# 2out_16A_bi_TS-ARM_V1_0.net
KiCad netlist of a schematic drawn in EAGLE
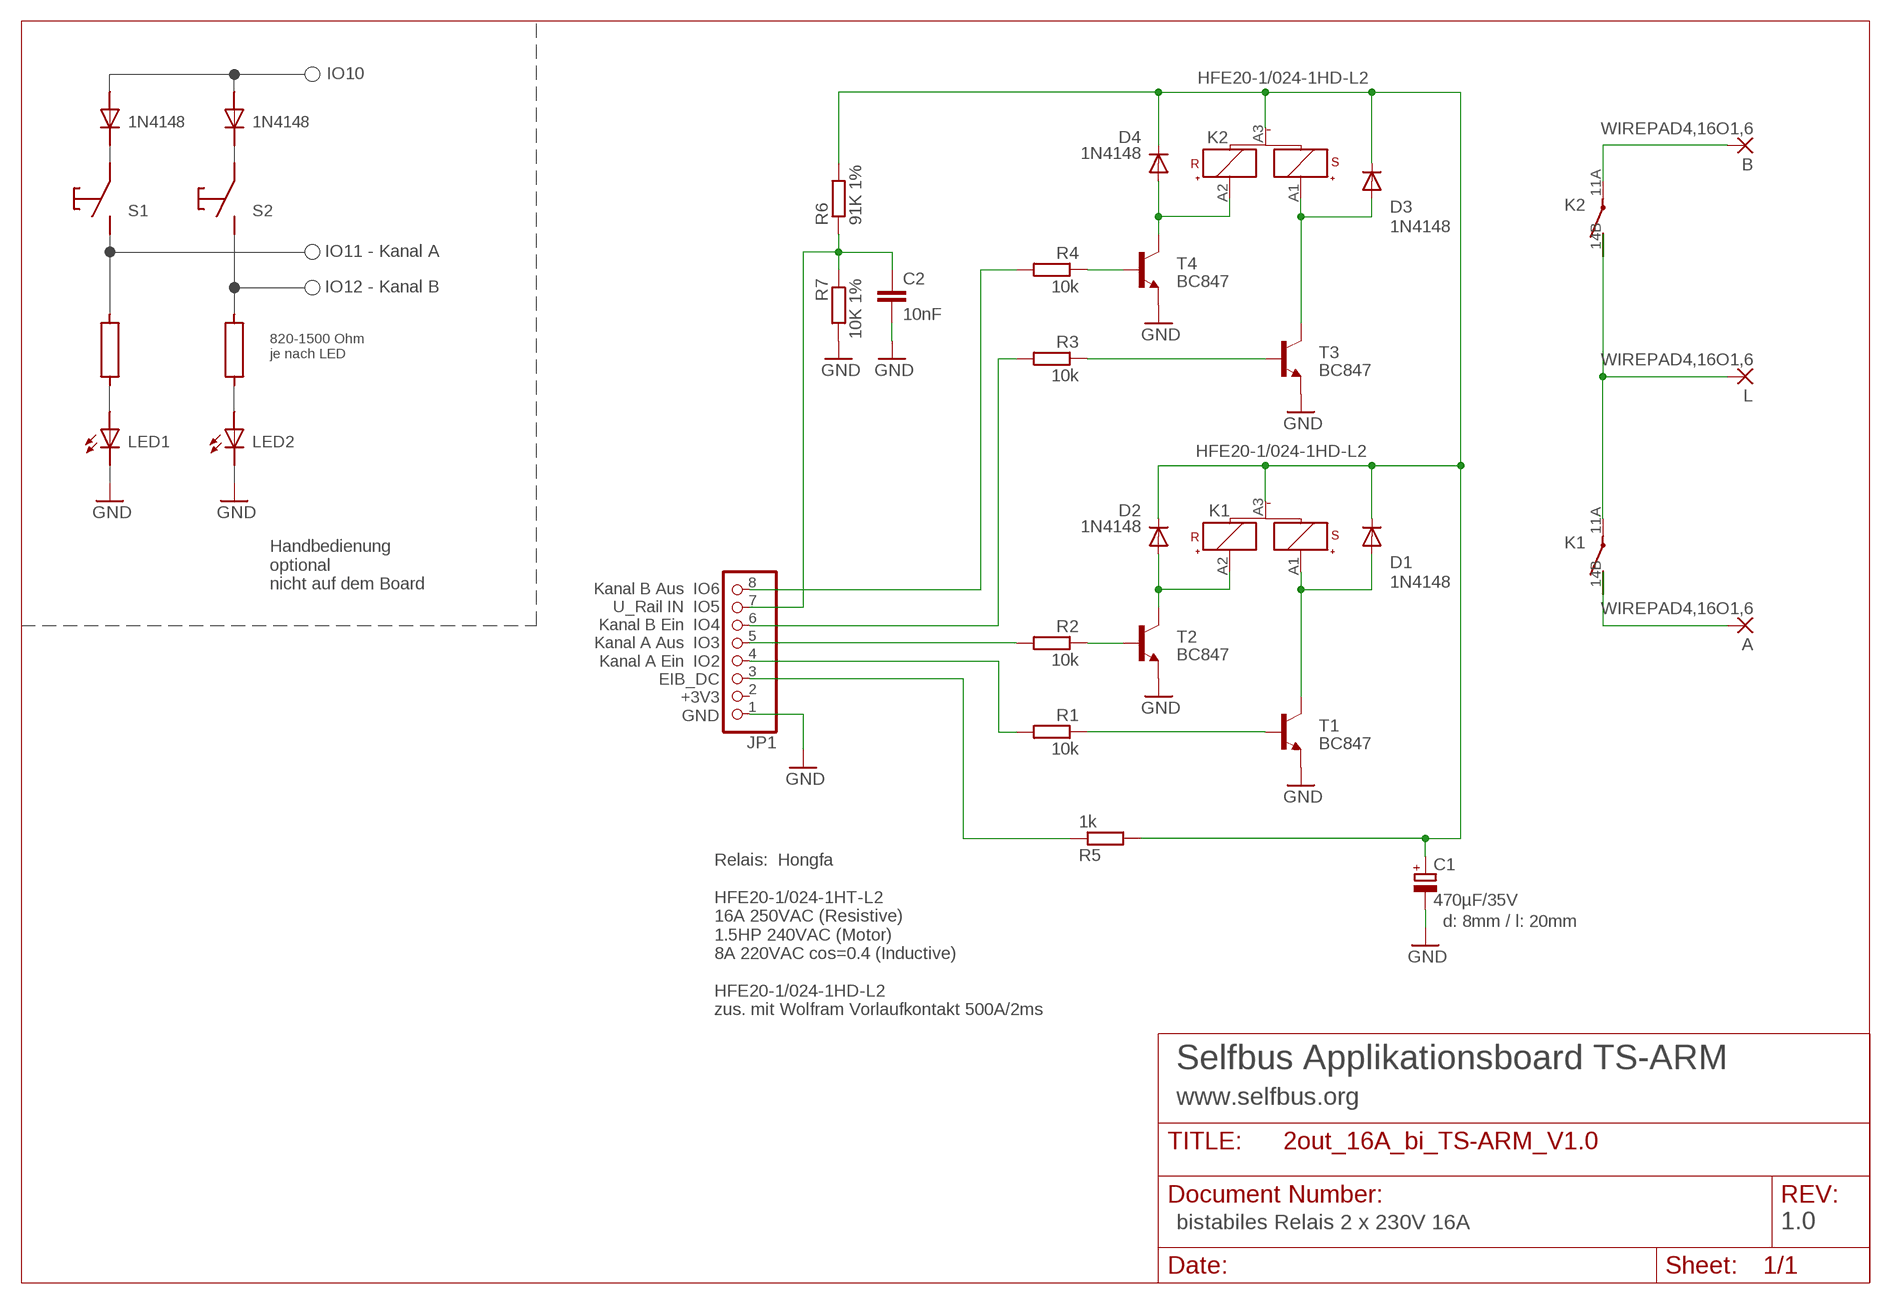
[diagram p0: schematic, sheet 1]

(export (version "E")
  (design (tool "Eeschema 10.0.6"))
  (components
    (comp (ref "A")
      (value "WIREPAD4,16O1,6")
      (footprint "eagle-import:4,16O1,6")
      (libsource (lib "eagle-import") (part "WIREPAD4,16O1,6"))
    )
    (comp (ref "B")
      (value "WIREPAD4,16O1,6")
      (footprint "eagle-import:4,16O1,6")
      (libsource (lib "eagle-import") (part "WIREPAD4,16O1,6"))
    )
    (comp (ref "C1")
      (value "470µF/35V")
      (footprint "eagle-import:E3,5-8")
      (libsource (lib "eagle-import") (part "CPOL-EUE3.5-8"))
    )
    (comp (ref "C2")
      (value "10nF")
      (footprint "eagle-import:C1206K")
      (libsource (lib "eagle-import") (part "C-EUC1206K"))
    )
    (comp (ref "D1")
      (value "1N4148")
      (footprint "eagle-import:MINIMELF")
      (libsource (lib "eagle-import") (part "DIODE-MINIMELF"))
    )
    (comp (ref "D2")
      (value "1N4148")
      (footprint "eagle-import:MINIMELF")
      (libsource (lib "eagle-import") (part "DIODE-MINIMELF"))
    )
    (comp (ref "D3")
      (value "1N4148")
      (footprint "eagle-import:MINIMELF")
      (libsource (lib "eagle-import") (part "DIODE-MINIMELF"))
    )
    (comp (ref "D4")
      (value "1N4148")
      (footprint "eagle-import:MINIMELF")
      (libsource (lib "eagle-import") (part "DIODE-MINIMELF"))
    )
    (comp (ref "JP1")
      (value "PINHD-1X8")
      (footprint "eagle-import:1X08")
      (libsource (lib "eagle-import") (part "PINHD-1X8"))
    )
    (comp (ref "K1")
      (value "HFE20-1/024-1HD-L2")
      (footprint "eagle-import:RT1-BI")
      (fields (field (name "MPN") "RT314F24"))
      (libsource (lib "eagle-import") (part "RT?F31424"))
    )
    (comp (ref "K2")
      (value "HFE20-1/024-1HD-L2")
      (footprint "eagle-import:RT1-BI")
      (fields (field (name "MPN") "RT314F24"))
      (libsource (lib "eagle-import") (part "RT?F31424"))
    )
    (comp (ref "L")
      (value "WIREPAD4,16O1,6")
      (footprint "eagle-import:4,16O1,6")
      (libsource (lib "eagle-import") (part "WIREPAD4,16O1,6"))
    )
    (comp (ref "R1")
      (value "10k")
      (footprint "eagle-import:M1206")
      (libsource (lib "eagle-import") (part "R-EU_M1206"))
    )
    (comp (ref "R2")
      (value "10k")
      (footprint "eagle-import:M1206")
      (libsource (lib "eagle-import") (part "R-EU_M1206"))
    )
    (comp (ref "R3")
      (value "10k")
      (footprint "eagle-import:M1206")
      (libsource (lib "eagle-import") (part "R-EU_M1206"))
    )
    (comp (ref "R4")
      (value "10k")
      (footprint "eagle-import:M1206")
      (libsource (lib "eagle-import") (part "R-EU_M1206"))
    )
    (comp (ref "R5")
      (value "1k")
      (footprint "eagle-import:M1206")
      (libsource (lib "eagle-import") (part "R-EU_M1206"))
    )
    (comp (ref "R6")
      (value "91K 1%")
      (footprint "eagle-import:M1206")
      (libsource (lib "eagle-import") (part "R-EU_M1206"))
    )
    (comp (ref "R7")
      (value "10K 1%")
      (footprint "eagle-import:M1206")
      (libsource (lib "eagle-import") (part "R-EU_M1206"))
    )
    (comp (ref "T1")
      (value "BC847")
      (footprint "eagle-import:SOT23")
      (libsource (lib "eagle-import") (part "BC847"))
    )
    (comp (ref "T2")
      (value "BC847")
      (footprint "eagle-import:SOT23")
      (libsource (lib "eagle-import") (part "BC847"))
    )
    (comp (ref "T3")
      (value "BC847")
      (footprint "eagle-import:SOT23")
      (libsource (lib "eagle-import") (part "BC847"))
    )
    (comp (ref "T4")
      (value "BC847")
      (footprint "eagle-import:SOT23")
      (libsource (lib "eagle-import") (part "BC847"))
    )
    (comp (ref "U$1")
      (value "R_NUR_SCHALTPLAN")
      (footprint "eagle-import:LEER")
      (libsource (lib "eagle-import") (part "R_NUR_SCHALTPLAN"))
    )
    (comp (ref "U$2")
      (value "TASTE_NUR_SCHALTPLAN")
      (footprint "eagle-import:LEER")
      (libsource (lib "eagle-import") (part "TASTE_NUR_SCHALTPLAN"))
    )
    (comp (ref "U$3")
      (value "LED_NUR_SCHALTPLAN")
      (footprint "eagle-import:LEER")
      (libsource (lib "eagle-import") (part "LED_NUR_SCHALTPLAN"))
    )
    (comp (ref "U$4")
      (value "DIODE_NUR_SCHALTPLAN")
      (footprint "eagle-import:LEER")
      (libsource (lib "eagle-import") (part "DIODE_NUR_SCHALTPLAN"))
    )
    (comp (ref "U$5")
      (value "R_NUR_SCHALTPLAN")
      (footprint "eagle-import:LEER")
      (libsource (lib "eagle-import") (part "R_NUR_SCHALTPLAN"))
    )
    (comp (ref "U$6")
      (value "TASTE_NUR_SCHALTPLAN")
      (footprint "eagle-import:LEER")
      (libsource (lib "eagle-import") (part "TASTE_NUR_SCHALTPLAN"))
    )
    (comp (ref "U$7")
      (value "LED_NUR_SCHALTPLAN")
      (footprint "eagle-import:LEER")
      (libsource (lib "eagle-import") (part "LED_NUR_SCHALTPLAN"))
    )
    (comp (ref "U$8")
      (value "DIODE_NUR_SCHALTPLAN")
      (footprint "eagle-import:LEER")
      (libsource (lib "eagle-import") (part "DIODE_NUR_SCHALTPLAN"))
    )
  )
  (nets
    (net (code "1") (name "GND") (class "Default")
      (node (ref "C1") (pin "-") (pinfunction "-_-") (pintype "passive"))
      (node (ref "C2") (pin "2") (pinfunction "2_2") (pintype "passive"))
      (node (ref "JP1") (pin "1") (pinfunction "1_1") (pintype "passive"))
      (node (ref "R7") (pin "2") (pinfunction "2_2") (pintype "passive"))
      (node (ref "T1") (pin "2") (pinfunction "E_2") (pintype "passive"))
      (node (ref "T2") (pin "2") (pinfunction "E_2") (pintype "passive"))
      (node (ref "T3") (pin "2") (pinfunction "E_2") (pintype "passive"))
      (node (ref "T4") (pin "2") (pinfunction "E_2") (pintype "passive"))
    )
    (net (code "2") (name "Net-(A-P)") (class "Default")
      (node (ref "A") (pin "1") (pinfunction "P_1") (pintype "passive"))
      (node (ref "K1") (pin "14B") (pinfunction "SA_14B") (pintype "passive"))
    )
    (net (code "3") (name "Net-(B-P)") (class "Default")
      (node (ref "B") (pin "1") (pinfunction "P_1") (pintype "passive"))
      (node (ref "K2") (pin "11A") (pinfunction "PA_11A") (pintype "passive"))
    )
    (net (code "4") (name "Net-(C2-Pad1)") (class "Default")
      (node (ref "C2") (pin "1") (pinfunction "1_1") (pintype "passive"))
      (node (ref "JP1") (pin "7") (pinfunction "7_7") (pintype "passive"))
      (node (ref "R6") (pin "1") (pinfunction "1_1") (pintype "passive"))
      (node (ref "R7") (pin "1") (pinfunction "1_1") (pintype "passive"))
    )
    (net (code "5") (name "Net-(JP1-Pad3)") (class "Default")
      (node (ref "JP1") (pin "3") (pinfunction "3_3") (pintype "passive"))
      (node (ref "R5") (pin "1") (pinfunction "1_1") (pintype "passive"))
    )
    (net (code "6") (name "Net-(JP1-Pad4)") (class "Default")
      (node (ref "JP1") (pin "4") (pinfunction "4_4") (pintype "passive"))
      (node (ref "R1") (pin "2") (pinfunction "2_2") (pintype "passive"))
    )
    (net (code "7") (name "Net-(JP1-Pad5)") (class "Default")
      (node (ref "JP1") (pin "5") (pinfunction "5_5") (pintype "passive"))
      (node (ref "R2") (pin "2") (pinfunction "2_2") (pintype "passive"))
    )
    (net (code "8") (name "Net-(JP1-Pad6)") (class "Default")
      (node (ref "JP1") (pin "6") (pinfunction "6_6") (pintype "passive"))
      (node (ref "R3") (pin "2") (pinfunction "2_2") (pintype "passive"))
    )
    (net (code "9") (name "Net-(JP1-Pad8)") (class "Default")
      (node (ref "JP1") (pin "8") (pinfunction "8_8") (pintype "passive"))
      (node (ref "R4") (pin "2") (pinfunction "2_2") (pintype "passive"))
    )
    (net (code "10") (name "Net-(K1A--)") (class "Default")
      (node (ref "C1") (pin "+") (pinfunction "+_+") (pintype "passive"))
      (node (ref "D1") (pin "C") (pinfunction "C_C") (pintype "passive"))
      (node (ref "D2") (pin "C") (pinfunction "C_C") (pintype "passive"))
      (node (ref "D3") (pin "C") (pinfunction "C_C") (pintype "passive"))
      (node (ref "D4") (pin "C") (pinfunction "C_C") (pintype "passive"))
      (node (ref "K1") (pin "A3") (pinfunction "-_A3") (pintype "passive"))
      (node (ref "K2") (pin "A3") (pinfunction "-_A3") (pintype "passive"))
      (node (ref "R5") (pin "2") (pinfunction "2_2") (pintype "passive"))
      (node (ref "R6") (pin "2") (pinfunction "2_2") (pintype "passive"))
    )
    (net (code "11") (name "Net-(K1A-R+)") (class "Default")
      (node (ref "D2") (pin "A") (pinfunction "A_A") (pintype "passive"))
      (node (ref "K1") (pin "A2") (pinfunction "R+_A2") (pintype "passive"))
      (node (ref "T2") (pin "3") (pinfunction "C_3") (pintype "passive"))
    )
    (net (code "12") (name "Net-(K1A-S+)") (class "Default")
      (node (ref "D1") (pin "A") (pinfunction "A_A") (pintype "passive"))
      (node (ref "K1") (pin "A1") (pinfunction "S+_A1") (pintype "passive"))
      (node (ref "T1") (pin "3") (pinfunction "C_3") (pintype "passive"))
    )
    (net (code "13") (name "Net-(K1B-PA)") (class "Default")
      (node (ref "K1") (pin "11A") (pinfunction "PA_11A") (pintype "passive"))
      (node (ref "K2") (pin "14B") (pinfunction "SA_14B") (pintype "passive"))
      (node (ref "L") (pin "1") (pinfunction "P_1") (pintype "passive"))
    )
    (net (code "14") (name "Net-(K2A-R+)") (class "Default")
      (node (ref "D4") (pin "A") (pinfunction "A_A") (pintype "passive"))
      (node (ref "K2") (pin "A2") (pinfunction "R+_A2") (pintype "passive"))
      (node (ref "T4") (pin "3") (pinfunction "C_3") (pintype "passive"))
    )
    (net (code "15") (name "Net-(K2A-S+)") (class "Default")
      (node (ref "D3") (pin "A") (pinfunction "A_A") (pintype "passive"))
      (node (ref "K2") (pin "A1") (pinfunction "S+_A1") (pintype "passive"))
      (node (ref "T3") (pin "3") (pinfunction "C_3") (pintype "passive"))
    )
    (net (code "16") (name "Net-(T1-B)") (class "Default")
      (node (ref "R1") (pin "1") (pinfunction "1_1") (pintype "passive"))
      (node (ref "T1") (pin "1") (pinfunction "B_1") (pintype "passive"))
    )
    (net (code "17") (name "Net-(T2-B)") (class "Default")
      (node (ref "R2") (pin "1") (pinfunction "1_1") (pintype "passive"))
      (node (ref "T2") (pin "1") (pinfunction "B_1") (pintype "passive"))
    )
    (net (code "18") (name "Net-(T3-B)") (class "Default")
      (node (ref "R3") (pin "1") (pinfunction "1_1") (pintype "passive"))
      (node (ref "T3") (pin "1") (pinfunction "B_1") (pintype "passive"))
    )
    (net (code "19") (name "Net-(T4-B)") (class "Default")
      (node (ref "R4") (pin "1") (pinfunction "1_1") (pintype "passive"))
      (node (ref "T4") (pin "1") (pinfunction "B_1") (pintype "passive"))
    )
    (net (code "20") (name "unconnected-(JP1-Pad2)") (class "Default")
      (node (ref "JP1") (pin "2") (pinfunction "2_2") (pintype "passive"))
    )
  )
)
